# LoRareceiver.net
KiCad netlist of a schematic drawn in EAGLE
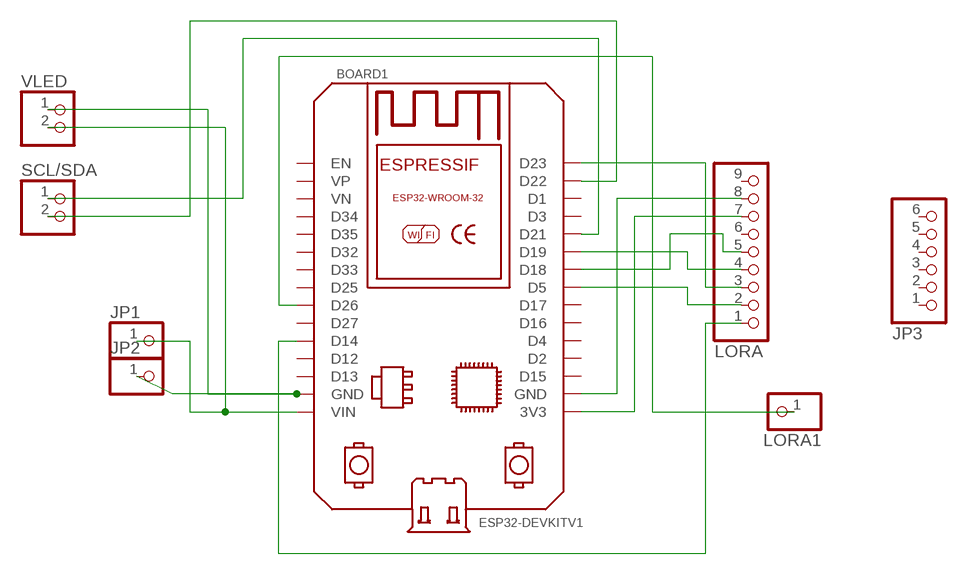
[diagram p0: schematic, sheet 1]

(export (version "E")
  (design (tool "Eeschema 10.0.6"))
  (components
    (comp (ref "BOARD1")
      (value "ESP32DEVKITV1")
      (footprint "eagle-import:ESP32-DEVKITV1")
      (libsource (lib "eagle-import") (part "ESP32DEVKITV1"))
    )
    (comp (ref "JP1")
      (value "PINHD-1X1")
      (footprint "eagle-import:1X01")
      (libsource (lib "eagle-import") (part "PINHD-1X1"))
    )
    (comp (ref "JP2")
      (value "PINHD-1X1")
      (footprint "eagle-import:1X01")
      (libsource (lib "eagle-import") (part "PINHD-1X1"))
    )
    (comp (ref "JP3")
      (value "PINHD-1X6")
      (footprint "eagle-import:1X06")
      (libsource (lib "eagle-import") (part "PINHD-1X6"))
    )
    (comp (ref "LORA")
      (value "PINHD-1X9")
      (footprint "eagle-import:1X09-BIG")
      (libsource (lib "eagle-import") (part "PINHD-1X9"))
    )
    (comp (ref "LORA1")
      (value "PINHD-1X1")
      (footprint "eagle-import:1X01")
      (libsource (lib "eagle-import") (part "PINHD-1X1"))
    )
    (comp (ref "SCL/SDA")
      (value "PINHD-1X2")
      (footprint "eagle-import:1X02")
      (libsource (lib "eagle-import") (part "PINHD-1X2"))
    )
    (comp (ref "VLED")
      (value "PINHD-1X2")
      (footprint "eagle-import:1X02")
      (libsource (lib "eagle-import") (part "PINHD-1X2"))
    )
  )
  (nets
    (net (code "1") (name "Net-(BOARD1-GND-PadGND@1)") (class "Default")
      (node (ref "BOARD1") (pin "GND@1") (pinfunction "GND_GND@1") (pintype "bidirectional"))
      (node (ref "LORA") (pin "8") (pinfunction "8_8") (pintype "passive"))
    )
    (net (code "2") (name "Net-(BOARD1-Pad3V3)") (class "Default")
      (node (ref "BOARD1") (pin "3V3") (pinfunction "3V3_3V3") (pintype "bidirectional"))
      (node (ref "LORA") (pin "7") (pinfunction "7_7") (pintype "passive"))
    )
    (net (code "3") (name "Net-(BOARD1-PadD5)") (class "Default")
      (node (ref "BOARD1") (pin "D5") (pinfunction "D5_D5") (pintype "bidirectional"))
      (node (ref "LORA") (pin "2") (pinfunction "2_2") (pintype "passive"))
    )
    (net (code "4") (name "Net-(BOARD1-PadD14)") (class "Default")
      (node (ref "BOARD1") (pin "D14") (pinfunction "D14_D14") (pintype "bidirectional"))
      (node (ref "LORA") (pin "1") (pinfunction "1_1") (pintype "passive"))
    )
    (net (code "5") (name "Net-(BOARD1-PadD18)") (class "Default")
      (node (ref "BOARD1") (pin "D18") (pinfunction "D18_D18") (pintype "bidirectional"))
      (node (ref "LORA") (pin "5") (pinfunction "5_5") (pintype "passive"))
    )
    (net (code "6") (name "Net-(BOARD1-PadD19)") (class "Default")
      (node (ref "BOARD1") (pin "D19") (pinfunction "D19_D19") (pintype "bidirectional"))
      (node (ref "LORA") (pin "4") (pinfunction "4_4") (pintype "passive"))
    )
    (net (code "7") (name "Net-(BOARD1-PadD21)") (class "Default")
      (node (ref "BOARD1") (pin "D21") (pinfunction "D21_D21") (pintype "bidirectional"))
      (node (ref "SCL/SDA") (pin "1") (pinfunction "1_1") (pintype "passive"))
    )
    (net (code "8") (name "Net-(BOARD1-PadD22)") (class "Default")
      (node (ref "BOARD1") (pin "D22") (pinfunction "D22_D22") (pintype "bidirectional"))
      (node (ref "SCL/SDA") (pin "2") (pinfunction "2_2") (pintype "passive"))
    )
    (net (code "9") (name "Net-(BOARD1-PadD23)") (class "Default")
      (node (ref "BOARD1") (pin "D23") (pinfunction "D23_D23") (pintype "bidirectional"))
      (node (ref "LORA") (pin "3") (pinfunction "3_3") (pintype "passive"))
    )
    (net (code "10") (name "Net-(BOARD1-PadD26)") (class "Default")
      (node (ref "BOARD1") (pin "D26") (pinfunction "D26_D26") (pintype "bidirectional"))
      (node (ref "LORA1") (pin "1") (pinfunction "1_1") (pintype "passive"))
    )
    (net (code "11") (name "Net-(BOARD1-PadGND)") (class "Default")
      (node (ref "BOARD1") (pin "GND") (pinfunction "GND_GND") (pintype "bidirectional"))
      (node (ref "JP2") (pin "1") (pinfunction "1_1") (pintype "passive"))
      (node (ref "VLED") (pin "1") (pinfunction "1_1") (pintype "passive"))
    )
    (net (code "12") (name "Net-(BOARD1-PadVIN)") (class "Default")
      (node (ref "BOARD1") (pin "VIN") (pinfunction "VIN_VIN") (pintype "bidirectional"))
      (node (ref "JP1") (pin "1") (pinfunction "1_1") (pintype "passive"))
      (node (ref "VLED") (pin "2") (pinfunction "2_2") (pintype "passive"))
    )
    (net (code "13") (name "unconnected-(BOARD1-PadD1)") (class "Default")
      (node (ref "BOARD1") (pin "D1") (pinfunction "D1_D1") (pintype "bidirectional"))
    )
    (net (code "14") (name "unconnected-(BOARD1-PadD2)") (class "Default")
      (node (ref "BOARD1") (pin "D2") (pinfunction "D2_D2") (pintype "bidirectional"))
    )
    (net (code "15") (name "unconnected-(BOARD1-PadD3)") (class "Default")
      (node (ref "BOARD1") (pin "D3") (pinfunction "D3_D3") (pintype "bidirectional"))
    )
    (net (code "16") (name "unconnected-(BOARD1-PadD4)") (class "Default")
      (node (ref "BOARD1") (pin "D4") (pinfunction "D4_D4") (pintype "bidirectional"))
    )
    (net (code "17") (name "unconnected-(BOARD1-PadD12)") (class "Default")
      (node (ref "BOARD1") (pin "D12") (pinfunction "D12_D12") (pintype "bidirectional"))
    )
    (net (code "18") (name "unconnected-(BOARD1-PadD13)") (class "Default")
      (node (ref "BOARD1") (pin "D13") (pinfunction "D13_D13") (pintype "bidirectional"))
    )
    (net (code "19") (name "unconnected-(BOARD1-PadD15)") (class "Default")
      (node (ref "BOARD1") (pin "D15") (pinfunction "D15_D15") (pintype "bidirectional"))
    )
    (net (code "20") (name "unconnected-(BOARD1-PadD16)") (class "Default")
      (node (ref "BOARD1") (pin "D16") (pinfunction "D16_D16") (pintype "bidirectional"))
    )
    (net (code "21") (name "unconnected-(BOARD1-PadD17)") (class "Default")
      (node (ref "BOARD1") (pin "D17") (pinfunction "D17_D17") (pintype "bidirectional"))
    )
    (net (code "22") (name "unconnected-(BOARD1-PadD25)") (class "Default")
      (node (ref "BOARD1") (pin "D25") (pinfunction "D25_D25") (pintype "bidirectional"))
    )
    (net (code "23") (name "unconnected-(BOARD1-PadD27)") (class "Default")
      (node (ref "BOARD1") (pin "D27") (pinfunction "D27_D27") (pintype "bidirectional"))
    )
    (net (code "24") (name "unconnected-(BOARD1-PadD32)") (class "Default")
      (node (ref "BOARD1") (pin "D32") (pinfunction "D32_D32") (pintype "bidirectional"))
    )
    (net (code "25") (name "unconnected-(BOARD1-PadD33)") (class "Default")
      (node (ref "BOARD1") (pin "D33") (pinfunction "D33_D33") (pintype "bidirectional"))
    )
    (net (code "26") (name "unconnected-(BOARD1-PadD34)") (class "Default")
      (node (ref "BOARD1") (pin "D34") (pinfunction "D34_D34") (pintype "bidirectional"))
    )
    (net (code "27") (name "unconnected-(BOARD1-PadD35)") (class "Default")
      (node (ref "BOARD1") (pin "D35") (pinfunction "D35_D35") (pintype "bidirectional"))
    )
    (net (code "28") (name "unconnected-(BOARD1-PadEN)") (class "Default")
      (node (ref "BOARD1") (pin "EN") (pinfunction "EN_EN") (pintype "bidirectional"))
    )
    (net (code "29") (name "unconnected-(BOARD1-PadVN)") (class "Default")
      (node (ref "BOARD1") (pin "VN") (pinfunction "VN_VN") (pintype "bidirectional"))
    )
    (net (code "30") (name "unconnected-(BOARD1-PadVP)") (class "Default")
      (node (ref "BOARD1") (pin "VP") (pinfunction "VP_VP") (pintype "bidirectional"))
    )
    (net (code "31") (name "unconnected-(JP3-Pad1)") (class "Default")
      (node (ref "JP3") (pin "1") (pinfunction "1_1") (pintype "passive"))
    )
    (net (code "32") (name "unconnected-(JP3-Pad2)") (class "Default")
      (node (ref "JP3") (pin "2") (pinfunction "2_2") (pintype "passive"))
    )
    (net (code "33") (name "unconnected-(JP3-Pad3)") (class "Default")
      (node (ref "JP3") (pin "3") (pinfunction "3_3") (pintype "passive"))
    )
    (net (code "34") (name "unconnected-(JP3-Pad4)") (class "Default")
      (node (ref "JP3") (pin "4") (pinfunction "4_4") (pintype "passive"))
    )
    (net (code "35") (name "unconnected-(JP3-Pad5)") (class "Default")
      (node (ref "JP3") (pin "5") (pinfunction "5_5") (pintype "passive"))
    )
    (net (code "36") (name "unconnected-(JP3-Pad6)") (class "Default")
      (node (ref "JP3") (pin "6") (pinfunction "6_6") (pintype "passive"))
    )
    (net (code "37") (name "unconnected-(LORA-Pad6)") (class "Default")
      (node (ref "LORA") (pin "6") (pinfunction "6_6") (pintype "passive"))
    )
    (net (code "38") (name "unconnected-(LORA-Pad9)") (class "Default")
      (node (ref "LORA") (pin "9") (pinfunction "9_9") (pintype "passive"))
    )
  )
)
